# WD1M_BTLE_JDY-08.net
KiCad netlist of a schematic drawn in EAGLE
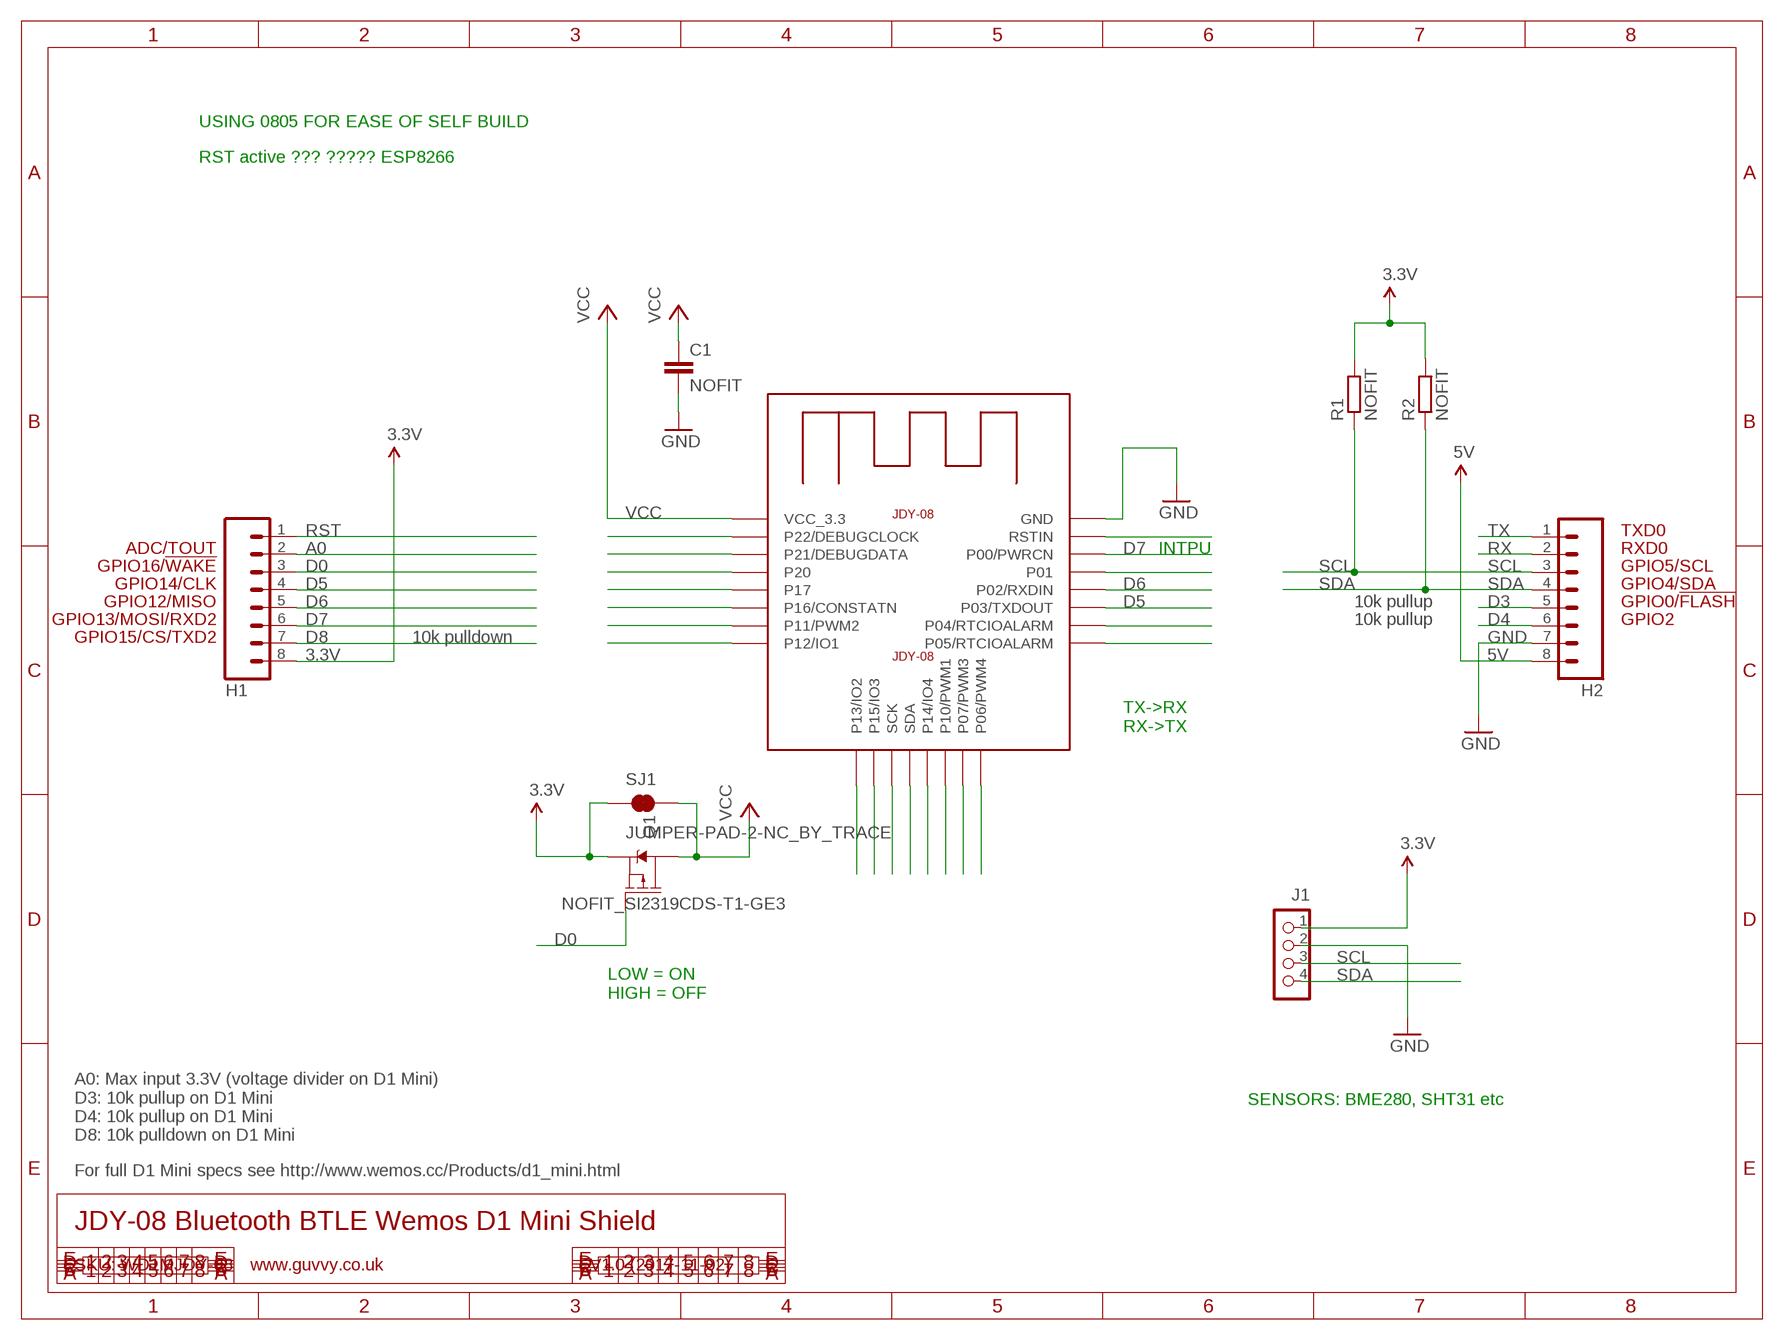
[diagram p0: schematic, sheet 1]

(export (version "E")
  (design (tool "Eeschema 10.0.6"))
  (components
    (comp (ref "C1")
      (value "NOFIT")
      (footprint "eagle-import:C0805K")
      (libsource (lib "eagle-import") (part "C-EUC0805K"))
    )
    (comp (ref "H1")
      (value "M08")
      (footprint "eagle-import:1X08")
      (libsource (lib "eagle-import") (part "M08"))
    )
    (comp (ref "H2")
      (value "M08")
      (footprint "eagle-import:1X08")
      (libsource (lib "eagle-import") (part "M08"))
    )
    (comp (ref "J1")
      (value "CON_HEADER_1X04")
      (footprint "eagle-import:M1X4")
      (libsource (lib "eagle-import") (part "CON_HEADER_1X04"))
    )
    (comp (ref "Q1")
      (value "NOFIT_SI2319CDS-T1-GE3")
      (footprint "eagle-import:SOT23-3")
      (libsource (lib "eagle-import") (part "MOSFET_PCH-IRLML2244"))
    )
    (comp (ref "R1")
      (value "NOFIT")
      (footprint "eagle-import:R0805")
      (libsource (lib "eagle-import") (part "R-EU_R0805"))
    )
    (comp (ref "R2")
      (value "NOFIT")
      (footprint "eagle-import:R0805")
      (libsource (lib "eagle-import") (part "R-EU_R0805"))
    )
    (comp (ref "SJ1")
      (value "JUMPER-PAD-2-NC_BY_TRACE")
      (footprint "eagle-import:PAD-JUMPER-2-NC_BY_TRACE_YES_SILK")
      (libsource (lib "eagle-import") (part "JUMPER-PAD-2-NC_BY_TRACE"))
    )
    (comp (ref "U$2")
      (value "JDY-08")
      (footprint "eagle-import:JDY-08")
      (libsource (lib "eagle-import") (part "JDY-08"))
    )
  )
  (nets
    (net (code "1") (name "/A0") (class "Default")
      (node (ref "H1") (pin "2") (pinfunction "2_2") (pintype "passive"))
    )
    (net (code "2") (name "/D0") (class "Default")
      (node (ref "H1") (pin "3") (pinfunction "3_3") (pintype "passive"))
      (node (ref "Q1") (pin "1") (pinfunction "G_1") (pintype "bidirectional"))
    )
    (net (code "3") (name "/D3") (class "Default")
      (node (ref "H2") (pin "5") (pinfunction "5_5") (pintype "passive"))
    )
    (net (code "4") (name "/D4") (class "Default")
      (node (ref "H2") (pin "6") (pinfunction "6_6") (pintype "passive"))
    )
    (net (code "5") (name "/D5") (class "Default")
      (node (ref "H1") (pin "4") (pinfunction "4_4") (pintype "passive"))
      (node (ref "U$2") (pin "P03/TXDOUT") (pinfunction "P03/TXDOUT_P03/TXDOUT") (pintype "bidirectional"))
    )
    (net (code "6") (name "/D6") (class "Default")
      (node (ref "H1") (pin "5") (pinfunction "5_5") (pintype "passive"))
      (node (ref "U$2") (pin "P02/RXDIN") (pinfunction "P02/RXDIN_P02/RXDIN") (pintype "bidirectional"))
    )
    (net (code "7") (name "/D7") (class "Default")
      (node (ref "H1") (pin "6") (pinfunction "6_6") (pintype "passive"))
      (node (ref "U$2") (pin "P00/PWRCN") (pinfunction "P00/PWRCN_P00/PWRCN") (pintype "bidirectional"))
    )
    (net (code "8") (name "/D8") (class "Default")
      (node (ref "H1") (pin "7") (pinfunction "7_7") (pintype "passive"))
    )
    (net (code "9") (name "/RST") (class "Default")
      (node (ref "H1") (pin "1") (pinfunction "1_1") (pintype "passive"))
    )
    (net (code "10") (name "/RX") (class "Default")
      (node (ref "H2") (pin "2") (pinfunction "2_2") (pintype "passive"))
    )
    (net (code "11") (name "/SCL") (class "Default")
      (node (ref "H2") (pin "3") (pinfunction "3_3") (pintype "passive"))
      (node (ref "J1") (pin "3") (pinfunction "3_3") (pintype "bidirectional"))
      (node (ref "R1") (pin "1") (pinfunction "1_1") (pintype "passive"))
    )
    (net (code "12") (name "/SDA") (class "Default")
      (node (ref "H2") (pin "4") (pinfunction "4_4") (pintype "passive"))
      (node (ref "J1") (pin "4") (pinfunction "4_4") (pintype "bidirectional"))
      (node (ref "R2") (pin "1") (pinfunction "1_1") (pintype "passive"))
    )
    (net (code "13") (name "/TX") (class "Default")
      (node (ref "H2") (pin "1") (pinfunction "1_1") (pintype "passive"))
    )
    (net (code "14") (name "3.3V") (class "Default")
      (node (ref "H1") (pin "8") (pinfunction "8_8") (pintype "passive"))
      (node (ref "J1") (pin "1") (pinfunction "1_1") (pintype "bidirectional"))
      (node (ref "Q1") (pin "2") (pinfunction "S_2") (pintype "bidirectional"))
      (node (ref "R1") (pin "2") (pinfunction "2_2") (pintype "passive"))
      (node (ref "R2") (pin "2") (pinfunction "2_2") (pintype "passive"))
      (node (ref "SJ1") (pin "1") (pinfunction "1_1") (pintype "passive"))
    )
    (net (code "15") (name "5V") (class "Default")
      (node (ref "H2") (pin "8") (pinfunction "8_8") (pintype "passive"))
    )
    (net (code "16") (name "GND") (class "Default")
      (node (ref "C1") (pin "2") (pinfunction "2_2") (pintype "passive"))
      (node (ref "H2") (pin "7") (pinfunction "7_7") (pintype "passive"))
      (node (ref "J1") (pin "2") (pinfunction "2_2") (pintype "bidirectional"))
      (node (ref "U$2") (pin "GND") (pinfunction "GND_GND") (pintype "bidirectional"))
    )
    (net (code "17") (name "VCC") (class "Default")
      (node (ref "C1") (pin "1") (pinfunction "1_1") (pintype "passive"))
      (node (ref "Q1") (pin "3") (pinfunction "D_3") (pintype "bidirectional"))
      (node (ref "SJ1") (pin "2") (pinfunction "2_2") (pintype "passive"))
      (node (ref "U$2") (pin "VCC_3.3") (pinfunction "VCC_3.3_VCC_3.3") (pintype "bidirectional"))
    )
    (net (code "18") (name "unconnected-(U$2-P04{slash}RTCIOALARM-PadP04{slash}RTCALARMIO)") (class "Default")
      (node (ref "U$2") (pin "P04/RTCALARMIO") (pinfunction "P04/RTCIOALARM_P04/RTCALARMIO") (pintype "bidirectional"))
    )
    (net (code "19") (name "unconnected-(U$2-P05{slash}RTCIOALARM-PadP05{slash}RTCALARMIO)") (class "Default")
      (node (ref "U$2") (pin "P05/RTCALARMIO") (pinfunction "P05/RTCIOALARM_P05/RTCALARMIO") (pintype "bidirectional"))
    )
    (net (code "20") (name "unconnected-(U$2-PadP01)") (class "Default")
      (node (ref "U$2") (pin "P01") (pinfunction "P01_P01") (pintype "bidirectional"))
    )
    (net (code "21") (name "unconnected-(U$2-PadP06{slash}PWM4)") (class "Default")
      (node (ref "U$2") (pin "P06/PWM4") (pinfunction "P06/PWM4_P06/PWM4") (pintype "bidirectional"))
    )
    (net (code "22") (name "unconnected-(U$2-PadP07{slash}PWM3)") (class "Default")
      (node (ref "U$2") (pin "P07/PWM3") (pinfunction "P07/PWM3_P07/PWM3") (pintype "bidirectional"))
    )
    (net (code "23") (name "unconnected-(U$2-PadP10{slash}PWM1)") (class "Default")
      (node (ref "U$2") (pin "P10/PWM1") (pinfunction "P10/PWM1_P10/PWM1") (pintype "bidirectional"))
    )
    (net (code "24") (name "unconnected-(U$2-PadP11{slash}PWM2)") (class "Default")
      (node (ref "U$2") (pin "P11/PWM2") (pinfunction "P11/PWM2_P11/PWM2") (pintype "bidirectional"))
    )
    (net (code "25") (name "unconnected-(U$2-PadP12{slash}IO1)") (class "Default")
      (node (ref "U$2") (pin "P12/IO1") (pinfunction "P12/IO1_P12/IO1") (pintype "bidirectional"))
    )
    (net (code "26") (name "unconnected-(U$2-PadP13{slash}IO2)") (class "Default")
      (node (ref "U$2") (pin "P13/IO2") (pinfunction "P13/IO2_P13/IO2") (pintype "bidirectional"))
    )
    (net (code "27") (name "unconnected-(U$2-PadP14{slash}IO4)") (class "Default")
      (node (ref "U$2") (pin "P14/IO4") (pinfunction "P14/IO4_P14/IO4") (pintype "bidirectional"))
    )
    (net (code "28") (name "unconnected-(U$2-PadP15{slash}IO3)") (class "Default")
      (node (ref "U$2") (pin "P15/IO3") (pinfunction "P15/IO3_P15/IO3") (pintype "bidirectional"))
    )
    (net (code "29") (name "unconnected-(U$2-PadP16{slash}CONSTATN)") (class "Default")
      (node (ref "U$2") (pin "P16/CONSTATN") (pinfunction "P16/CONSTATN_P16/CONSTATN") (pintype "bidirectional"))
    )
    (net (code "30") (name "unconnected-(U$2-PadP17)") (class "Default")
      (node (ref "U$2") (pin "P17") (pinfunction "P17_P17") (pintype "bidirectional"))
    )
    (net (code "31") (name "unconnected-(U$2-PadP20)") (class "Default")
      (node (ref "U$2") (pin "P20") (pinfunction "P20_P20") (pintype "bidirectional"))
    )
    (net (code "32") (name "unconnected-(U$2-PadP21{slash}DEBUGDATA)") (class "Default")
      (node (ref "U$2") (pin "P21/DEBUGDATA") (pinfunction "P21/DEBUGDATA_P21/DEBUGDATA") (pintype "bidirectional"))
    )
    (net (code "33") (name "unconnected-(U$2-PadP22{slash}DEBUGCLOCK)") (class "Default")
      (node (ref "U$2") (pin "P22/DEBUGCLOCK") (pinfunction "P22/DEBUGCLOCK_P22/DEBUGCLOCK") (pintype "bidirectional"))
    )
    (net (code "34") (name "unconnected-(U$2-PadRSTIN)") (class "Default")
      (node (ref "U$2") (pin "RSTIN") (pinfunction "RSTIN_RSTIN") (pintype "bidirectional"))
    )
    (net (code "35") (name "unconnected-(U$2-PadSCK)") (class "Default")
      (node (ref "U$2") (pin "SCK") (pinfunction "SCK_SCK") (pintype "bidirectional"))
    )
    (net (code "36") (name "unconnected-(U$2-PadSDA)") (class "Default")
      (node (ref "U$2") (pin "SDA") (pinfunction "SDA_SDA") (pintype "bidirectional"))
    )
  )
)
